# 4_Controller_A20_BUFFERs.net
KiCad netlist of a schematic drawn in Altium Designer
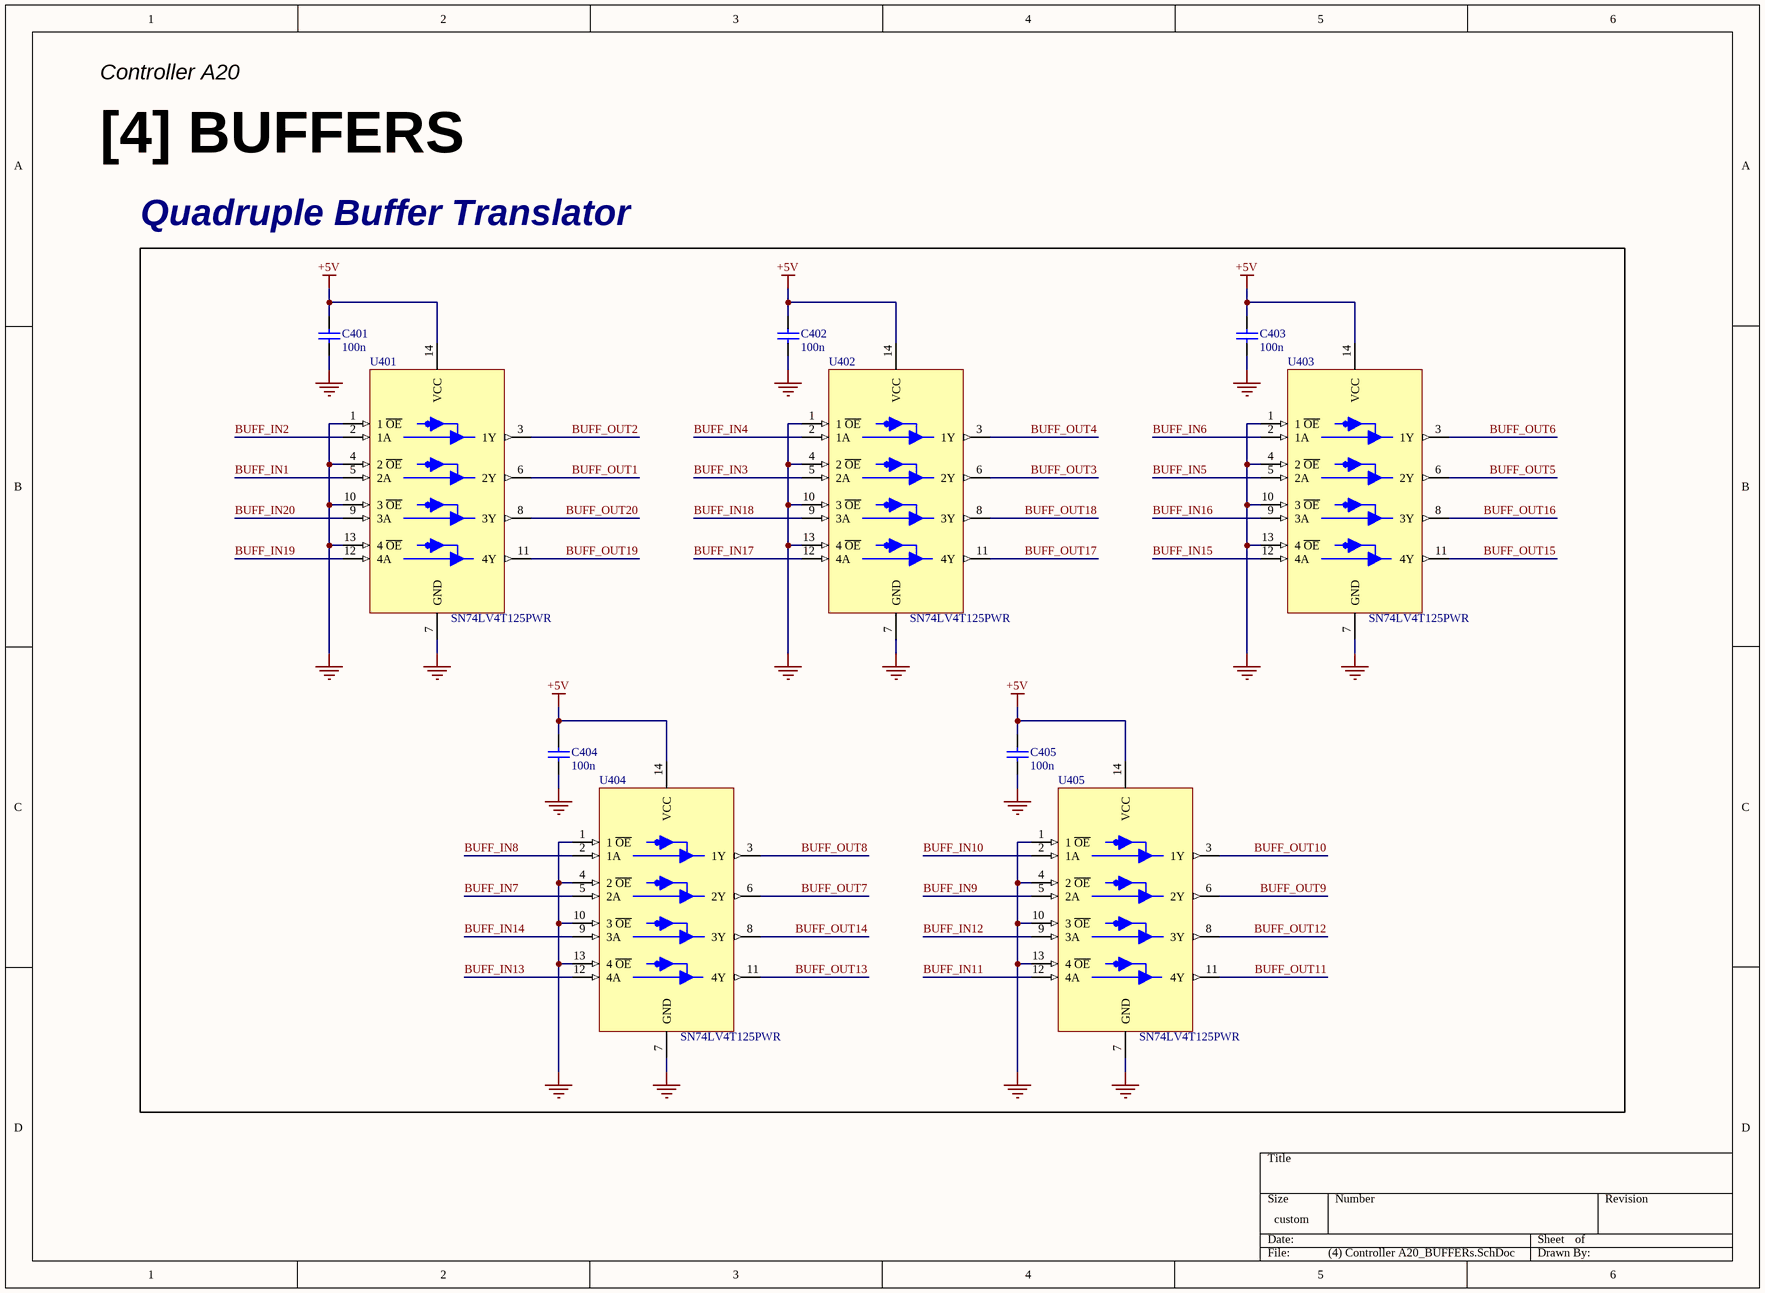
[diagram p0: (4) Controller A20_BUFFERs.SchDoc]

(export (version "E")
  (design (tool "Eeschema 10.0.6"))
  (components
    (comp (ref "C401")
      (value "100n")
      (footprint "C0603")
      (description "0.1 µF ±10% 50V Ceramic Capacitor X7R 0603 (1608 Metric)")
      (fields (field (name "MANUFACTURER") "KEMET") (field (name "MFR. PART #") "C0603C104K5RACTU"))
      (libsource (lib "Symbols") (part "CAP 100nF 50V"))
    )
    (comp (ref "C402")
      (value "100n")
      (footprint "C0603")
      (description "0.1 µF ±10% 50V Ceramic Capacitor X7R 0603 (1608 Metric)")
      (fields (field (name "MANUFACTURER") "KEMET") (field (name "MFR. PART #") "C0603C104K5RACTU"))
      (libsource (lib "Symbols") (part "CAP 100nF 50V"))
    )
    (comp (ref "C403")
      (value "100n")
      (footprint "C0603")
      (description "0.1 µF ±10% 50V Ceramic Capacitor X7R 0603 (1608 Metric)")
      (fields (field (name "MANUFACTURER") "KEMET") (field (name "MFR. PART #") "C0603C104K5RACTU"))
      (libsource (lib "Symbols") (part "CAP 100nF 50V"))
    )
    (comp (ref "C404")
      (value "100n")
      (footprint "C0603")
      (description "0.1 µF ±10% 50V Ceramic Capacitor X7R 0603 (1608 Metric)")
      (fields (field (name "MANUFACTURER") "KEMET") (field (name "MFR. PART #") "C0603C104K5RACTU"))
      (libsource (lib "Symbols") (part "CAP 100nF 50V"))
    )
    (comp (ref "C405")
      (value "100n")
      (footprint "C0603")
      (description "0.1 µF ±10% 50V Ceramic Capacitor X7R 0603 (1608 Metric)")
      (fields (field (name "MANUFACTURER") "KEMET") (field (name "MFR. PART #") "C0603C104K5RACTU"))
      (libsource (lib "Symbols") (part "CAP 100nF 50V"))
    )
    (comp (ref "U401")
      (value "SN74LV4T125PWR")
      (footprint "14-TSSOP")
      (description "Buffer, Non-Inverting 4 Element 1 Bit per Element 3-State Output 14-TSSOP")
      (fields (field (name "MANUFACTURER") "Texas Instruments"))
      (libsource (lib "Symbols") (part "SN74LV4T125PWR Non-Inverting Buffer"))
    )
    (comp (ref "U402")
      (value "SN74LV4T125PWR")
      (footprint "14-TSSOP")
      (description "Buffer, Non-Inverting 4 Element 1 Bit per Element 3-State Output 14-TSSOP")
      (fields (field (name "MANUFACTURER") "Texas Instruments"))
      (libsource (lib "Symbols") (part "SN74LV4T125PWR Non-Inverting Buffer"))
    )
    (comp (ref "U403")
      (value "SN74LV4T125PWR")
      (footprint "14-TSSOP")
      (description "Buffer, Non-Inverting 4 Element 1 Bit per Element 3-State Output 14-TSSOP")
      (fields (field (name "MANUFACTURER") "Texas Instruments"))
      (libsource (lib "Symbols") (part "SN74LV4T125PWR Non-Inverting Buffer"))
    )
    (comp (ref "U404")
      (value "SN74LV4T125PWR")
      (footprint "14-TSSOP")
      (description "Buffer, Non-Inverting 4 Element 1 Bit per Element 3-State Output 14-TSSOP")
      (fields (field (name "MANUFACTURER") "Texas Instruments"))
      (libsource (lib "Symbols") (part "SN74LV4T125PWR Non-Inverting Buffer"))
    )
    (comp (ref "U405")
      (value "SN74LV4T125PWR")
      (footprint "14-TSSOP")
      (description "Buffer, Non-Inverting 4 Element 1 Bit per Element 3-State Output 14-TSSOP")
      (fields (field (name "MANUFACTURER") "Texas Instruments"))
      (libsource (lib "Symbols") (part "SN74LV4T125PWR Non-Inverting Buffer"))
    )
  )
  (nets
    (net (code "1") (name "+5V") (class "Default")
      (node (ref "C401") (pin "2") (pinfunction "2_2") (pintype "passive"))
      (node (ref "C402") (pin "2") (pinfunction "2_2") (pintype "passive"))
      (node (ref "C403") (pin "2") (pinfunction "2_2") (pintype "passive"))
      (node (ref "C404") (pin "2") (pinfunction "2_2") (pintype "passive"))
      (node (ref "C405") (pin "2") (pinfunction "2_2") (pintype "passive"))
      (node (ref "U401") (pin "14") (pinfunction "VCC_14") (pintype "power_in"))
      (node (ref "U402") (pin "14") (pinfunction "VCC_14") (pintype "power_in"))
      (node (ref "U403") (pin "14") (pinfunction "VCC_14") (pintype "power_in"))
      (node (ref "U404") (pin "14") (pinfunction "VCC_14") (pintype "power_in"))
      (node (ref "U405") (pin "14") (pinfunction "VCC_14") (pintype "power_in"))
    )
    (net (code "2") (name "/BUFF_IN1") (class "Default")
      (node (ref "U401") (pin "5") (pinfunction "2A_5") (pintype "input"))
    )
    (net (code "3") (name "/BUFF_IN2") (class "Default")
      (node (ref "U401") (pin "2") (pinfunction "1A_2") (pintype "input"))
    )
    (net (code "4") (name "/BUFF_IN3") (class "Default")
      (node (ref "U402") (pin "5") (pinfunction "2A_5") (pintype "input"))
    )
    (net (code "5") (name "/BUFF_IN4") (class "Default")
      (node (ref "U402") (pin "2") (pinfunction "1A_2") (pintype "input"))
    )
    (net (code "6") (name "/BUFF_IN5") (class "Default")
      (node (ref "U403") (pin "5") (pinfunction "2A_5") (pintype "input"))
    )
    (net (code "7") (name "/BUFF_IN6") (class "Default")
      (node (ref "U403") (pin "2") (pinfunction "1A_2") (pintype "input"))
    )
    (net (code "8") (name "/BUFF_IN7") (class "Default")
      (node (ref "U404") (pin "5") (pinfunction "2A_5") (pintype "input"))
    )
    (net (code "9") (name "/BUFF_IN8") (class "Default")
      (node (ref "U404") (pin "2") (pinfunction "1A_2") (pintype "input"))
    )
    (net (code "10") (name "/BUFF_IN9") (class "Default")
      (node (ref "U405") (pin "5") (pinfunction "2A_5") (pintype "input"))
    )
    (net (code "11") (name "/BUFF_IN10") (class "Default")
      (node (ref "U405") (pin "2") (pinfunction "1A_2") (pintype "input"))
    )
    (net (code "12") (name "/BUFF_IN11") (class "Default")
      (node (ref "U405") (pin "12") (pinfunction "4A_12") (pintype "input"))
    )
    (net (code "13") (name "/BUFF_IN12") (class "Default")
      (node (ref "U405") (pin "9") (pinfunction "3A_9") (pintype "input"))
    )
    (net (code "14") (name "/BUFF_IN13") (class "Default")
      (node (ref "U404") (pin "12") (pinfunction "4A_12") (pintype "input"))
    )
    (net (code "15") (name "/BUFF_IN14") (class "Default")
      (node (ref "U404") (pin "9") (pinfunction "3A_9") (pintype "input"))
    )
    (net (code "16") (name "/BUFF_IN15") (class "Default")
      (node (ref "U403") (pin "12") (pinfunction "4A_12") (pintype "input"))
    )
    (net (code "17") (name "/BUFF_IN16") (class "Default")
      (node (ref "U403") (pin "9") (pinfunction "3A_9") (pintype "input"))
    )
    (net (code "18") (name "/BUFF_IN17") (class "Default")
      (node (ref "U402") (pin "12") (pinfunction "4A_12") (pintype "input"))
    )
    (net (code "19") (name "/BUFF_IN18") (class "Default")
      (node (ref "U402") (pin "9") (pinfunction "3A_9") (pintype "input"))
    )
    (net (code "20") (name "/BUFF_IN19") (class "Default")
      (node (ref "U401") (pin "12") (pinfunction "4A_12") (pintype "input"))
    )
    (net (code "21") (name "/BUFF_IN20") (class "Default")
      (node (ref "U401") (pin "9") (pinfunction "3A_9") (pintype "input"))
    )
    (net (code "22") (name "/BUFF_OUT1") (class "Default")
      (node (ref "U401") (pin "6") (pinfunction "2Y_6") (pintype "output"))
    )
    (net (code "23") (name "/BUFF_OUT2") (class "Default")
      (node (ref "U401") (pin "3") (pinfunction "1Y_3") (pintype "output"))
    )
    (net (code "24") (name "/BUFF_OUT3") (class "Default")
      (node (ref "U402") (pin "6") (pinfunction "2Y_6") (pintype "output"))
    )
    (net (code "25") (name "/BUFF_OUT4") (class "Default")
      (node (ref "U402") (pin "3") (pinfunction "1Y_3") (pintype "output"))
    )
    (net (code "26") (name "/BUFF_OUT5") (class "Default")
      (node (ref "U403") (pin "6") (pinfunction "2Y_6") (pintype "output"))
    )
    (net (code "27") (name "/BUFF_OUT6") (class "Default")
      (node (ref "U403") (pin "3") (pinfunction "1Y_3") (pintype "output"))
    )
    (net (code "28") (name "/BUFF_OUT7") (class "Default")
      (node (ref "U404") (pin "6") (pinfunction "2Y_6") (pintype "output"))
    )
    (net (code "29") (name "/BUFF_OUT8") (class "Default")
      (node (ref "U404") (pin "3") (pinfunction "1Y_3") (pintype "output"))
    )
    (net (code "30") (name "/BUFF_OUT9") (class "Default")
      (node (ref "U405") (pin "6") (pinfunction "2Y_6") (pintype "output"))
    )
    (net (code "31") (name "/BUFF_OUT10") (class "Default")
      (node (ref "U405") (pin "3") (pinfunction "1Y_3") (pintype "output"))
    )
    (net (code "32") (name "/BUFF_OUT11") (class "Default")
      (node (ref "U405") (pin "11") (pinfunction "4Y_11") (pintype "output"))
    )
    (net (code "33") (name "/BUFF_OUT12") (class "Default")
      (node (ref "U405") (pin "8") (pinfunction "3Y_8") (pintype "output"))
    )
    (net (code "34") (name "/BUFF_OUT13") (class "Default")
      (node (ref "U404") (pin "11") (pinfunction "4Y_11") (pintype "output"))
    )
    (net (code "35") (name "/BUFF_OUT14") (class "Default")
      (node (ref "U404") (pin "8") (pinfunction "3Y_8") (pintype "output"))
    )
    (net (code "36") (name "/BUFF_OUT15") (class "Default")
      (node (ref "U403") (pin "11") (pinfunction "4Y_11") (pintype "output"))
    )
    (net (code "37") (name "/BUFF_OUT16") (class "Default")
      (node (ref "U403") (pin "8") (pinfunction "3Y_8") (pintype "output"))
    )
    (net (code "38") (name "/BUFF_OUT17") (class "Default")
      (node (ref "U402") (pin "11") (pinfunction "4Y_11") (pintype "output"))
    )
    (net (code "39") (name "/BUFF_OUT18") (class "Default")
      (node (ref "U402") (pin "8") (pinfunction "3Y_8") (pintype "output"))
    )
    (net (code "40") (name "/BUFF_OUT19") (class "Default")
      (node (ref "U401") (pin "11") (pinfunction "4Y_11") (pintype "output"))
    )
    (net (code "41") (name "/BUFF_OUT20") (class "Default")
      (node (ref "U401") (pin "8") (pinfunction "3Y_8") (pintype "output"))
    )
    (net (code "42") (name "GND") (class "Default")
      (node (ref "C401") (pin "1") (pinfunction "1_1") (pintype "passive"))
      (node (ref "C402") (pin "1") (pinfunction "1_1") (pintype "passive"))
      (node (ref "C403") (pin "1") (pinfunction "1_1") (pintype "passive"))
      (node (ref "C404") (pin "1") (pinfunction "1_1") (pintype "passive"))
      (node (ref "C405") (pin "1") (pinfunction "1_1") (pintype "passive"))
      (node (ref "U401") (pin "1") (pinfunction "1_~{OE}_1") (pintype "input"))
      (node (ref "U401") (pin "10") (pinfunction "3_~{OE}_10") (pintype "input"))
      (node (ref "U401") (pin "13") (pinfunction "4_~{OE}_13") (pintype "input"))
      (node (ref "U401") (pin "4") (pinfunction "2_~{OE}_4") (pintype "input"))
      (node (ref "U401") (pin "7") (pinfunction "GND_7") (pintype "power_in"))
      (node (ref "U402") (pin "1") (pinfunction "1_~{OE}_1") (pintype "input"))
      (node (ref "U402") (pin "10") (pinfunction "3_~{OE}_10") (pintype "input"))
      (node (ref "U402") (pin "13") (pinfunction "4_~{OE}_13") (pintype "input"))
      (node (ref "U402") (pin "4") (pinfunction "2_~{OE}_4") (pintype "input"))
      (node (ref "U402") (pin "7") (pinfunction "GND_7") (pintype "power_in"))
      (node (ref "U403") (pin "1") (pinfunction "1_~{OE}_1") (pintype "input"))
      (node (ref "U403") (pin "10") (pinfunction "3_~{OE}_10") (pintype "input"))
      (node (ref "U403") (pin "13") (pinfunction "4_~{OE}_13") (pintype "input"))
      (node (ref "U403") (pin "4") (pinfunction "2_~{OE}_4") (pintype "input"))
      (node (ref "U403") (pin "7") (pinfunction "GND_7") (pintype "power_in"))
      (node (ref "U404") (pin "1") (pinfunction "1_~{OE}_1") (pintype "input"))
      (node (ref "U404") (pin "10") (pinfunction "3_~{OE}_10") (pintype "input"))
      (node (ref "U404") (pin "13") (pinfunction "4_~{OE}_13") (pintype "input"))
      (node (ref "U404") (pin "4") (pinfunction "2_~{OE}_4") (pintype "input"))
      (node (ref "U404") (pin "7") (pinfunction "GND_7") (pintype "power_in"))
      (node (ref "U405") (pin "1") (pinfunction "1_~{OE}_1") (pintype "input"))
      (node (ref "U405") (pin "10") (pinfunction "3_~{OE}_10") (pintype "input"))
      (node (ref "U405") (pin "13") (pinfunction "4_~{OE}_13") (pintype "input"))
      (node (ref "U405") (pin "4") (pinfunction "2_~{OE}_4") (pintype "input"))
      (node (ref "U405") (pin "7") (pinfunction "GND_7") (pintype "power_in"))
    )
  )
)
